# just_a_switch-mk-2_0.net
KiCad netlist of a schematic drawn in EAGLE
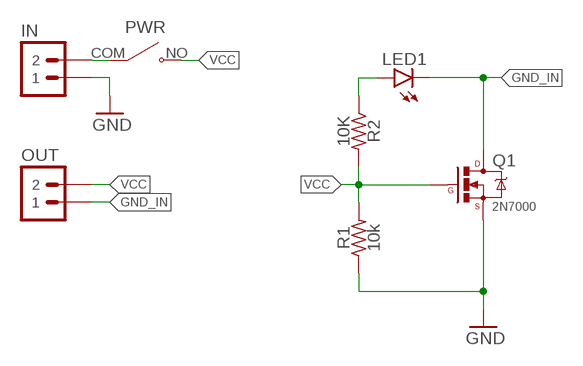
[diagram p0: schematic, sheet 1]

(export (version "E")
  (design (tool "Eeschema 10.0.6"))
  (components
    (comp (ref "IN")
      (value "M02PTH-CENTERED-R+")
      (footprint "eagle-import:1X02-CENTER-R+")
      (libsource (lib "eagle-import") (part "M02PTH-CENTERED-R+"))
    )
    (comp (ref "LED1")
      (value "LED3MM-LESS")
      (footprint "eagle-import:LED3MM-LESSSILK")
      (libsource (lib "eagle-import") (part "LED3MM-LESS"))
    )
    (comp (ref "OUT")
      (value "M02PTH-CENTERED-R+")
      (footprint "eagle-import:1X02-CENTER-R+")
      (libsource (lib "eagle-import") (part "M02PTH-CENTERED-R+"))
    )
    (comp (ref "PWR")
      (value "SWITCH-SPSTROCKER")
      (footprint "eagle-import:SPST-ROCKER-3.81MM")
      (libsource (lib "eagle-import") (part "SWITCH-SPSTROCKER"))
    )
    (comp (ref "Q1")
      (value "2N7000")
      (footprint "eagle-import:TO-92-AMMO")
      (libsource (lib "eagle-import") (part "MOSFET-NCHANNEL2N7000-AMMO"))
    )
    (comp (ref "R1")
      (value "10k")
      (footprint "eagle-import:RESISTOR-AXIAL-PTH-5.08MM")
      (libsource (lib "eagle-import") (part "RESISTORPTH-AXIAL-5.08MM"))
    )
    (comp (ref "R2")
      (value "10K")
      (footprint "eagle-import:RESISTOR-AXIAL-PTH-5.08MM")
      (libsource (lib "eagle-import") (part "RESISTORPTH-AXIAL-5.08MM"))
    )
  )
  (nets
    (net (code "1") (name "GND") (class "Default")
      (node (ref "IN") (pin "1") (pinfunction "1_1") (pintype "passive"))
      (node (ref "Q1") (pin "1") (pinfunction "S_1") (pintype "passive"))
      (node (ref "R1") (pin "P$1") (pinfunction "1_P$1") (pintype "passive"))
    )
    (net (code "2") (name "GND_IN") (class "Default")
      (node (ref "LED1") (pin "K") (pinfunction "C_K") (pintype "passive"))
      (node (ref "OUT") (pin "1") (pinfunction "1_1") (pintype "passive"))
      (node (ref "Q1") (pin "3") (pinfunction "D_3") (pintype "passive"))
    )
    (net (code "3") (name "Net-(IN-Pad2)") (class "Default")
      (node (ref "IN") (pin "2") (pinfunction "2_2") (pintype "passive"))
      (node (ref "PWR") (pin "COM") (pinfunction "COM_COM") (pintype "bidirectional"))
    )
    (net (code "4") (name "Net-(R2-1)") (class "Default")
      (node (ref "LED1") (pin "A") (pinfunction "A_A") (pintype "passive"))
      (node (ref "R2") (pin "P$1") (pinfunction "1_P$1") (pintype "passive"))
    )
    (net (code "5") (name "VCC") (class "Default")
      (node (ref "OUT") (pin "2") (pinfunction "2_2") (pintype "passive"))
      (node (ref "PWR") (pin "NO") (pinfunction "NO_NO") (pintype "bidirectional"))
      (node (ref "Q1") (pin "2") (pinfunction "G_2") (pintype "passive"))
      (node (ref "R1") (pin "P$2") (pinfunction "2_P$2") (pintype "passive"))
      (node (ref "R2") (pin "P$2") (pinfunction "2_P$2") (pintype "passive"))
    )
  )
)
